# Papra_v0_20.net
KiCad netlist of a schematic drawn in EAGLE
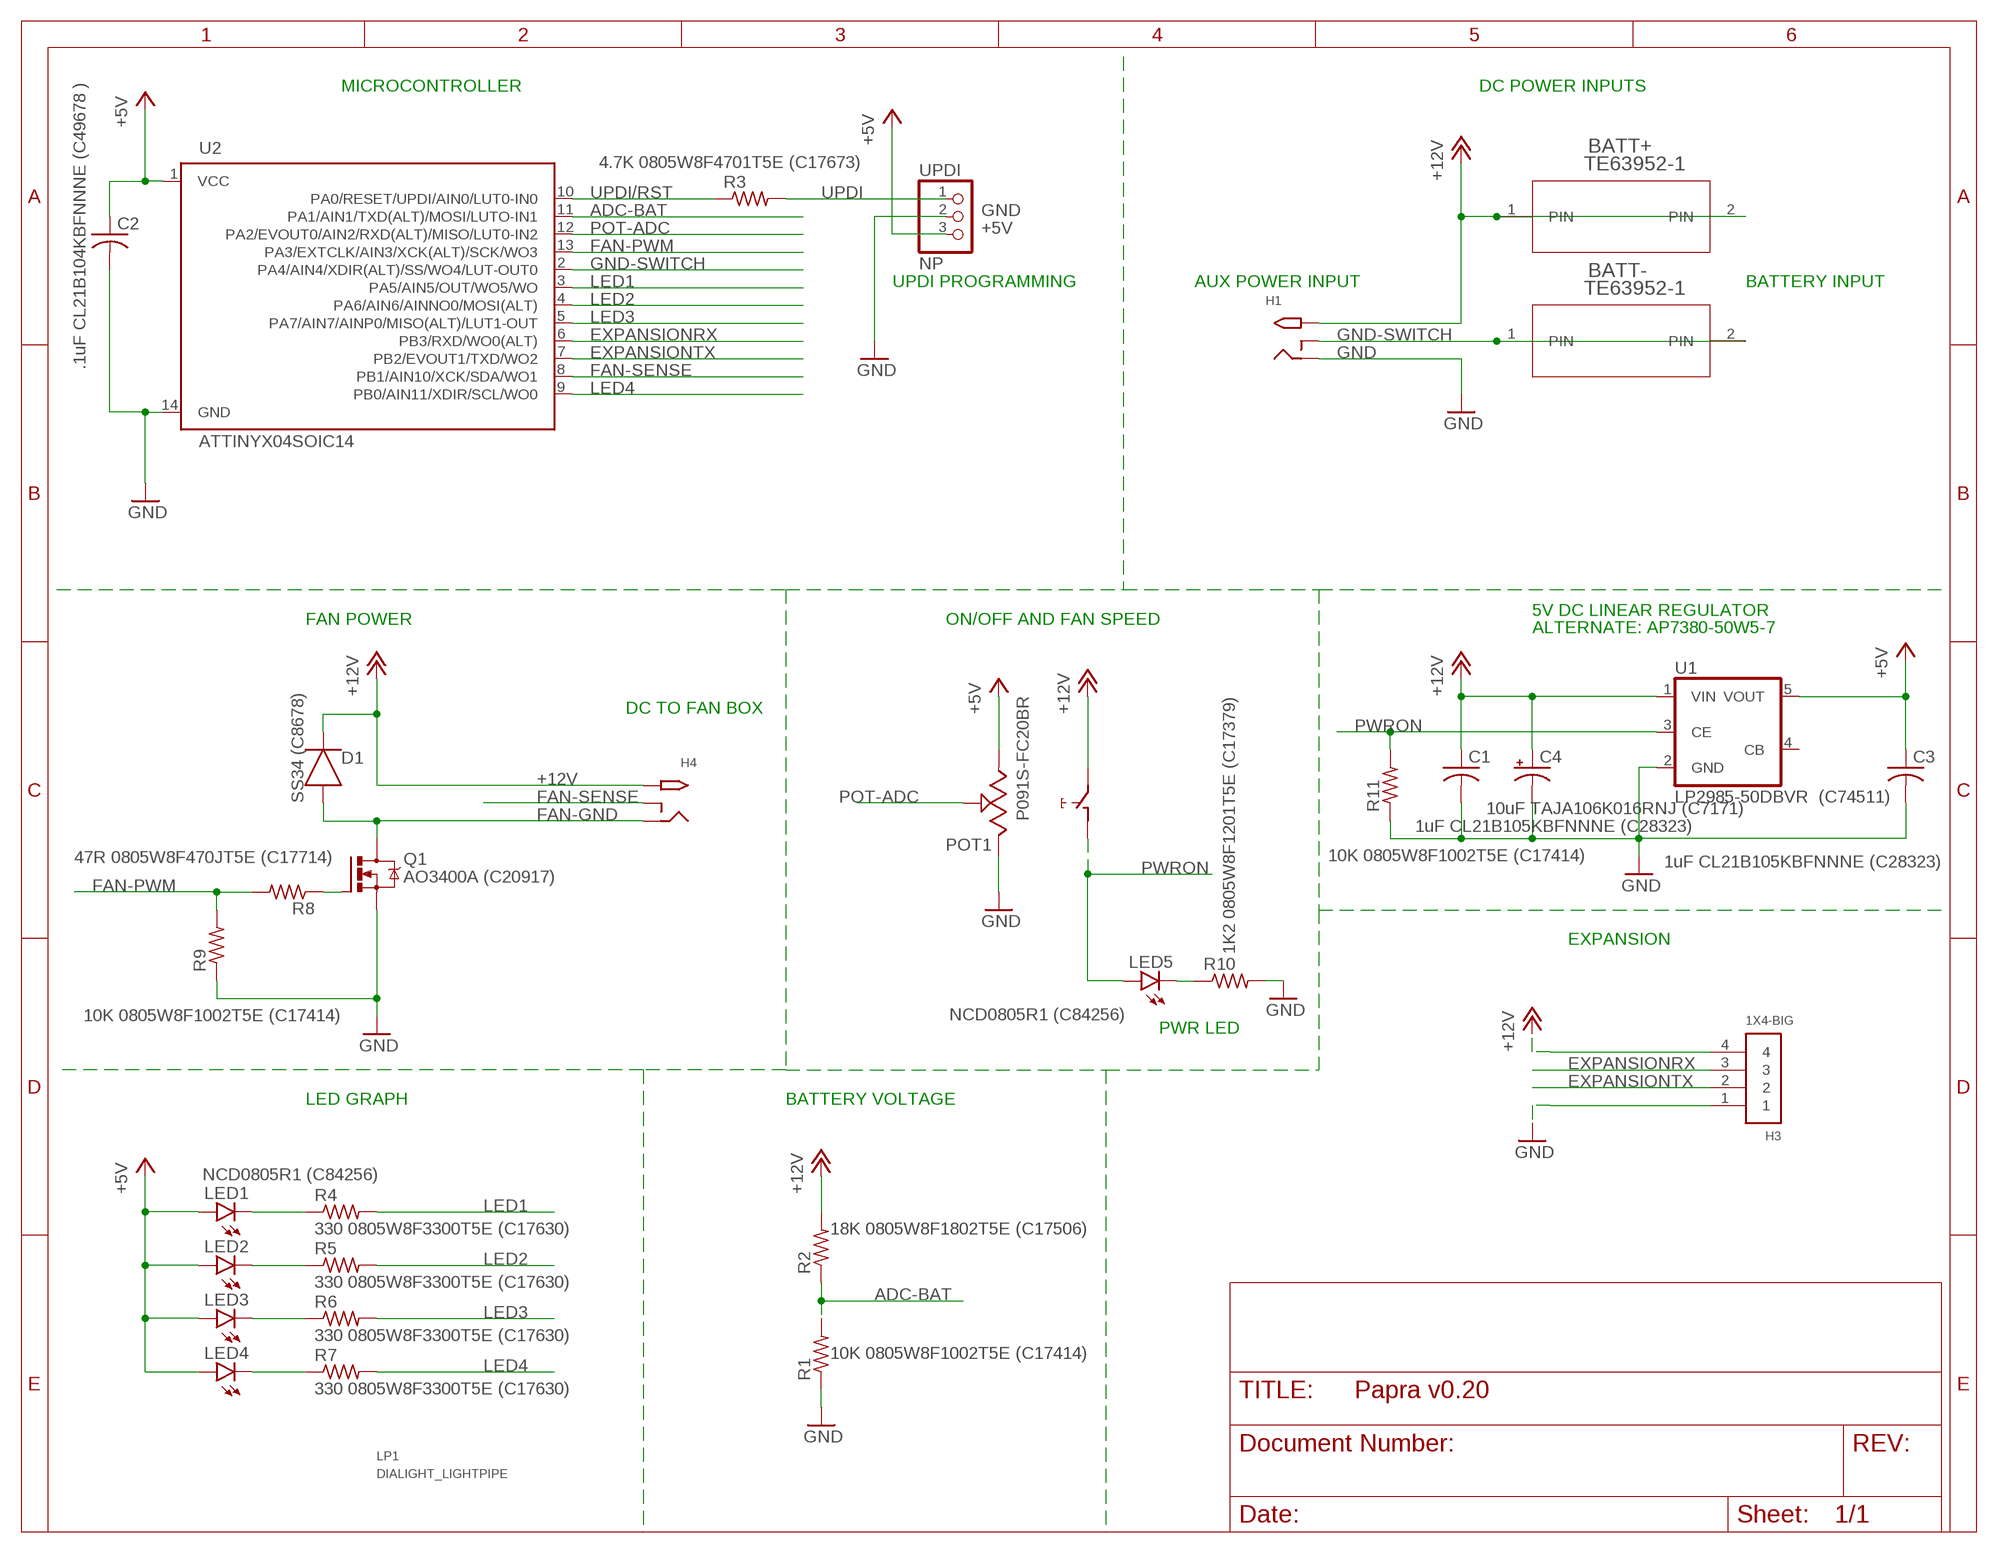
[diagram p0: schematic, sheet 1]

(export (version "E")
  (design (tool "Eeschema 10.0.6"))
  (components
    (comp (ref "BATT+")
      (value "TE63952-1")
      (footprint "eagle-import:TE63952-1")
      (libsource (lib "eagle-import") (part "TE63952-1"))
    )
    (comp (ref "BATT-")
      (value "TE63952-1")
      (footprint "eagle-import:TE63952-1")
      (libsource (lib "eagle-import") (part "TE63952-1"))
    )
    (comp (ref "C1")
      (value "1uF CL21B105KBFNNNE (C28323)")
      (footprint "eagle-import:C0805")
      (libsource (lib "eagle-import") (part "C-USC0805"))
    )
    (comp (ref "C2")
      (value ".1uF CL21B104KBFNNNE (C49678 )")
      (footprint "eagle-import:C0805")
      (libsource (lib "eagle-import") (part "C-USC0805"))
    )
    (comp (ref "C3")
      (value "1uF CL21B105KBFNNNE (C28323)")
      (footprint "eagle-import:C0805")
      (libsource (lib "eagle-import") (part "C-USC0805"))
    )
    (comp (ref "C4")
      (value "10uF TAJA106K016RNJ (C7171)")
      (footprint "eagle-import:A_3216-18R")
      (libsource (lib "eagle-import") (part "CPOL-USA/3216-18R"))
    )
    (comp (ref "D1")
      (value "SS34 (C8678)")
      (footprint "eagle-import:DIOM5226X290N")
      (libsource (lib "eagle-import") (part "DIODEDO-214AC(SMA)"))
    )
    (comp (ref "H1")
      (value "M-CUI-PJ-066A")
      (footprint "eagle-import:DCJACK-PJ-066A")
      (libsource (lib "eagle-import") (part "PJ-066A"))
    )
    (comp (ref "H3")
      (value "1X4-BIG")
      (footprint "eagle-import:1X04-BIG")
      (libsource (lib "eagle-import") (part "1X4-BIG"))
    )
    (comp (ref "H4")
      (value "M-CUI-PJ-066A")
      (footprint "eagle-import:DCJACK-PJ-066A")
      (libsource (lib "eagle-import") (part "PJ-066A"))
    )
    (comp (ref "LED1")
      (value "NCD0805R1 (C84256)")
      (footprint "eagle-import:CHIPLED_0805")
      (libsource (lib "eagle-import") (part "LEDCHIPLED_0805"))
    )
    (comp (ref "LED2")
      (value "NCD0805R1 (C84256)")
      (footprint "eagle-import:CHIPLED_0805")
      (libsource (lib "eagle-import") (part "LEDCHIPLED_0805"))
    )
    (comp (ref "LED3")
      (value "NCD0805R1 (C84256)")
      (footprint "eagle-import:CHIPLED_0805")
      (libsource (lib "eagle-import") (part "LEDCHIPLED_0805"))
    )
    (comp (ref "LED4")
      (value "NCD0805R1 (C84256)")
      (footprint "eagle-import:CHIPLED_0805")
      (libsource (lib "eagle-import") (part "LEDCHIPLED_0805"))
    )
    (comp (ref "LED5")
      (value "NCD0805R1 (C84256)")
      (footprint "eagle-import:CHIPLED_0805")
      (libsource (lib "eagle-import") (part "LEDCHIPLED_0805"))
    )
    (comp (ref "LP1")
      (value "DIALIGHT_LIGHTPIPE")
      (footprint "eagle-import:DIALIGHT_5151020F__LEDS")
      (libsource (lib "eagle-import") (part "DIALIGHT_LIGHTPIPE"))
    )
    (comp (ref "POT1")
      (value "P091S-FC20BR")
      (footprint "eagle-import:P091S-FC20BR")
      (libsource (lib "eagle-import") (part "P091S-FC20BR"))
    )
    (comp (ref "Q1")
      (value "AO3400A (C20917)")
      (footprint "eagle-import:SOT23")
      (fields (field (name "MANUFACTURER") "ON Semiconductor") (field (name "MPN") "BSS123L"))
      (libsource (lib "eagle-import") (part "NMOSFET_-SOT23BSS123"))
    )
    (comp (ref "R1")
      (value "10K 0805W8F1002T5E (C17414)")
      (footprint "eagle-import:R0805")
      (libsource (lib "eagle-import") (part "R-US_R0805"))
    )
    (comp (ref "R2")
      (value "18K 0805W8F1802T5E (C17506)")
      (footprint "eagle-import:R0805")
      (libsource (lib "eagle-import") (part "R-US_R0805"))
    )
    (comp (ref "R3")
      (value "4.7K 0805W8F4701T5E (C17673)")
      (footprint "eagle-import:R0805")
      (libsource (lib "eagle-import") (part "R-US_R0805"))
    )
    (comp (ref "R4")
      (value "330 0805W8F3300T5E (C17630)")
      (footprint "eagle-import:R0805")
      (libsource (lib "eagle-import") (part "R-US_R0805"))
    )
    (comp (ref "R5")
      (value "330 0805W8F3300T5E (C17630)")
      (footprint "eagle-import:R0805")
      (libsource (lib "eagle-import") (part "R-US_R0805"))
    )
    (comp (ref "R6")
      (value "330 0805W8F3300T5E (C17630)")
      (footprint "eagle-import:R0805")
      (libsource (lib "eagle-import") (part "R-US_R0805"))
    )
    (comp (ref "R7")
      (value "330 0805W8F3300T5E (C17630)")
      (footprint "eagle-import:R0805")
      (libsource (lib "eagle-import") (part "R-US_R0805"))
    )
    (comp (ref "R8")
      (value "47R 0805W8F470JT5E (C17714)")
      (footprint "eagle-import:R0805")
      (libsource (lib "eagle-import") (part "R-US_R0805"))
    )
    (comp (ref "R9")
      (value "10K 0805W8F1002T5E (C17414)")
      (footprint "eagle-import:R0805")
      (libsource (lib "eagle-import") (part "R-US_R0805"))
    )
    (comp (ref "R10")
      (value "1K2 0805W8F1201T5E (C17379)")
      (footprint "eagle-import:R0805")
      (libsource (lib "eagle-import") (part "R-US_R0805"))
    )
    (comp (ref "R11")
      (value "10K 0805W8F1002T5E (C17414)")
      (footprint "eagle-import:R0805")
      (libsource (lib "eagle-import") (part "R-US_R0805"))
    )
    (comp (ref "U1")
      (value "LP2985-50DBVR (C74511)")
      (footprint "eagle-import:SOT25")
      (libsource (lib "eagle-import") (part "TS520533"))
    )
    (comp (ref "U2")
      (value "ATTINYX04SOIC14")
      (footprint "eagle-import:SOIC127P600X144-14")
      (libsource (lib "eagle-import") (part "ATTINYX04SOIC14"))
    )
    (comp (ref "UPDI")
      (value "NP")
      (footprint "eagle-import:1X03")
      (libsource (lib "eagle-import") (part "PINHD-1X3"))
    )
  )
  (nets
    (net (code "1") (name "+5V") (class "Default")
      (node (ref "C2") (pin "1") (pinfunction "1_1") (pintype "passive"))
      (node (ref "C3") (pin "1") (pinfunction "1_1") (pintype "passive"))
      (node (ref "LED1") (pin "A") (pinfunction "A_A") (pintype "passive"))
      (node (ref "LED2") (pin "A") (pinfunction "A_A") (pintype "passive"))
      (node (ref "LED3") (pin "A") (pinfunction "A_A") (pintype "passive"))
      (node (ref "LED4") (pin "A") (pinfunction "A_A") (pintype "passive"))
      (node (ref "POT1") (pin "1") (pinfunction "1_1") (pintype "passive"))
      (node (ref "U1") (pin "5") (pinfunction "VOUT_5") (pintype "passive"))
      (node (ref "U2") (pin "1") (pinfunction "VCC_1") (pintype "power_in"))
      (node (ref "UPDI") (pin "3") (pinfunction "3_3") (pintype "passive"))
    )
    (net (code "2") (name "+12V") (class "Default")
      (node (ref "BATT+") (pin "1") (pinfunction "PIN_1") (pintype "passive"))
      (node (ref "BATT+") (pin "2") (pinfunction "PIN_2") (pintype "passive"))
      (node (ref "C1") (pin "1") (pinfunction "1_1") (pintype "passive"))
      (node (ref "C4") (pin "+") (pinfunction "+_+") (pintype "passive"))
      (node (ref "D1") (pin "1") (pinfunction "C_1") (pintype "passive"))
      (node (ref "H1") (pin "PWR") (pinfunction "TIP_PWR") (pintype "bidirectional"))
      (node (ref "H3") (pin "4") (pinfunction "4_4") (pintype "bidirectional"))
      (node (ref "H4") (pin "PWR") (pinfunction "TIP_PWR") (pintype "bidirectional"))
      (node (ref "POT1") (pin "NO") (pinfunction "5_NO") (pintype "passive"))
      (node (ref "R2") (pin "2") (pinfunction "2_2") (pintype "passive"))
      (node (ref "U1") (pin "1") (pinfunction "VIN_1") (pintype "input"))
    )
    (net (code "3") (name "/ADC-BAT") (class "Default")
      (node (ref "R1") (pin "2") (pinfunction "2_2") (pintype "passive"))
      (node (ref "R2") (pin "1") (pinfunction "1_1") (pintype "passive"))
      (node (ref "U2") (pin "11") (pinfunction "PA1/AIN1/TXD(ALT)/MOSI/LUTO-IN1_11") (pintype "bidirectional"))
    )
    (net (code "4") (name "/EXPANSIONRX") (class "Default")
      (node (ref "H3") (pin "3") (pinfunction "3_3") (pintype "bidirectional"))
      (node (ref "U2") (pin "6") (pinfunction "PB3/RXD/WO0(ALT)_6") (pintype "bidirectional"))
    )
    (net (code "5") (name "/EXPANSIONTX") (class "Default")
      (node (ref "H3") (pin "2") (pinfunction "2_2") (pintype "bidirectional"))
      (node (ref "U2") (pin "7") (pinfunction "PB2/EVOUT1/TXD/WO2_7") (pintype "bidirectional"))
    )
    (net (code "6") (name "/FAN-GND") (class "Default")
      (node (ref "D1") (pin "2") (pinfunction "A_2") (pintype "passive"))
      (node (ref "H4") (pin "GND") (pinfunction "RING_GND") (pintype "bidirectional"))
      (node (ref "Q1") (pin "3") (pinfunction "D_3") (pintype "passive"))
    )
    (net (code "7") (name "/FAN-PWM") (class "Default")
      (node (ref "R8") (pin "2") (pinfunction "2_2") (pintype "passive"))
      (node (ref "R9") (pin "2") (pinfunction "2_2") (pintype "passive"))
      (node (ref "U2") (pin "13") (pinfunction "PA3/EXTCLK/AIN3/XCK(ALT)/SCK/WO3_13") (pintype "bidirectional"))
    )
    (net (code "8") (name "/FAN-SENSE") (class "Default")
      (node (ref "H4") (pin "GNDBREAK") (pinfunction "RING_SW_GNDBREAK") (pintype "bidirectional"))
      (node (ref "U2") (pin "8") (pinfunction "PB1/AIN10/XCK/SDA/WO1_8") (pintype "bidirectional"))
    )
    (net (code "9") (name "/GND-SWITCH") (class "Default")
      (node (ref "BATT-") (pin "1") (pinfunction "PIN_1") (pintype "passive"))
      (node (ref "BATT-") (pin "2") (pinfunction "PIN_2") (pintype "passive"))
      (node (ref "H1") (pin "GNDBREAK") (pinfunction "RING_SW_GNDBREAK") (pintype "bidirectional"))
      (node (ref "U2") (pin "2") (pinfunction "PA4/AIN4/XDIR(ALT)/SS/WO4/LUT-OUT0_2") (pintype "bidirectional"))
    )
    (net (code "10") (name "/LED1") (class "Default")
      (node (ref "R4") (pin "2") (pinfunction "2_2") (pintype "passive"))
      (node (ref "U2") (pin "3") (pinfunction "PA5/AIN5/OUT/WO5/WO_3") (pintype "bidirectional"))
    )
    (net (code "11") (name "/LED2") (class "Default")
      (node (ref "R5") (pin "2") (pinfunction "2_2") (pintype "passive"))
      (node (ref "U2") (pin "4") (pinfunction "PA6/AIN6/AINNO0/MOSI(ALT)_4") (pintype "bidirectional"))
    )
    (net (code "12") (name "/LED3") (class "Default")
      (node (ref "R6") (pin "2") (pinfunction "2_2") (pintype "passive"))
      (node (ref "U2") (pin "5") (pinfunction "PA7/AIN7/AINP0/MISO(ALT)/LUT1-OUT_5") (pintype "bidirectional"))
    )
    (net (code "13") (name "/LED4") (class "Default")
      (node (ref "R7") (pin "2") (pinfunction "2_2") (pintype "passive"))
      (node (ref "U2") (pin "9") (pinfunction "PB0/AIN11/XDIR/SCL/WO0_9") (pintype "bidirectional"))
    )
    (net (code "14") (name "/POT-ADC") (class "Default")
      (node (ref "POT1") (pin "2") (pinfunction "2_2") (pintype "passive"))
      (node (ref "U2") (pin "12") (pinfunction "PA2/EVOUT0/AIN2/RXD(ALT)/MISO/LUT0-IN2_12") (pintype "bidirectional"))
    )
    (net (code "15") (name "/PWRON") (class "Default")
      (node (ref "LED5") (pin "A") (pinfunction "A_A") (pintype "passive"))
      (node (ref "POT1") (pin "COM") (pinfunction "4_COM") (pintype "passive"))
      (node (ref "R11") (pin "2") (pinfunction "2_2") (pintype "passive"))
      (node (ref "U1") (pin "3") (pinfunction "CE_3") (pintype "input"))
    )
    (net (code "16") (name "/UPDI") (class "Default")
      (node (ref "R3") (pin "2") (pinfunction "2_2") (pintype "passive"))
      (node (ref "UPDI") (pin "1") (pinfunction "1_1") (pintype "passive"))
    )
    (net (code "17") (name "/UPDI{slash}RST") (class "Default")
      (node (ref "R3") (pin "1") (pinfunction "1_1") (pintype "passive"))
      (node (ref "U2") (pin "10") (pinfunction "PA0/RESET/UPDI/AIN0/LUT0-IN0_10") (pintype "bidirectional"))
    )
    (net (code "18") (name "GND") (class "Default")
      (node (ref "C1") (pin "2") (pinfunction "2_2") (pintype "passive"))
      (node (ref "C2") (pin "2") (pinfunction "2_2") (pintype "passive"))
      (node (ref "C3") (pin "2") (pinfunction "2_2") (pintype "passive"))
      (node (ref "C4") (pin "-") (pinfunction "-_-") (pintype "passive"))
      (node (ref "H1") (pin "GND") (pinfunction "RING_GND") (pintype "bidirectional"))
      (node (ref "H3") (pin "1") (pinfunction "1_1") (pintype "bidirectional"))
      (node (ref "POT1") (pin "3") (pinfunction "3_3") (pintype "passive"))
      (node (ref "Q1") (pin "2") (pinfunction "S_2") (pintype "passive"))
      (node (ref "R1") (pin "1") (pinfunction "1_1") (pintype "passive"))
      (node (ref "R10") (pin "2") (pinfunction "2_2") (pintype "passive"))
      (node (ref "R11") (pin "1") (pinfunction "1_1") (pintype "passive"))
      (node (ref "R9") (pin "1") (pinfunction "1_1") (pintype "passive"))
      (node (ref "U1") (pin "2") (pinfunction "GND_2") (pintype "passive"))
      (node (ref "U2") (pin "14") (pinfunction "GND_14") (pintype "power_in"))
      (node (ref "UPDI") (pin "2") (pinfunction "2_2") (pintype "passive"))
    )
    (net (code "19") (name "Net-(LED1-PadC)") (class "Default")
      (node (ref "LED1") (pin "C") (pinfunction "C_C") (pintype "passive"))
      (node (ref "R4") (pin "1") (pinfunction "1_1") (pintype "passive"))
    )
    (net (code "20") (name "Net-(LED2-PadC)") (class "Default")
      (node (ref "LED2") (pin "C") (pinfunction "C_C") (pintype "passive"))
      (node (ref "R5") (pin "1") (pinfunction "1_1") (pintype "passive"))
    )
    (net (code "21") (name "Net-(LED3-PadC)") (class "Default")
      (node (ref "LED3") (pin "C") (pinfunction "C_C") (pintype "passive"))
      (node (ref "R6") (pin "1") (pinfunction "1_1") (pintype "passive"))
    )
    (net (code "22") (name "Net-(LED4-PadC)") (class "Default")
      (node (ref "LED4") (pin "C") (pinfunction "C_C") (pintype "passive"))
      (node (ref "R7") (pin "1") (pinfunction "1_1") (pintype "passive"))
    )
    (net (code "23") (name "Net-(LED5-PadC)") (class "Default")
      (node (ref "LED5") (pin "C") (pinfunction "C_C") (pintype "passive"))
      (node (ref "R10") (pin "1") (pinfunction "1_1") (pintype "passive"))
    )
    (net (code "24") (name "Net-(Q1-G)") (class "Default")
      (node (ref "Q1") (pin "1") (pinfunction "G_1") (pintype "passive"))
      (node (ref "R8") (pin "1") (pinfunction "1_1") (pintype "passive"))
    )
    (net (code "25") (name "unconnected-(U1-CB-Pad4)") (class "Default")
      (node (ref "U1") (pin "4") (pinfunction "CB_4") (pintype "input"))
    )
  )
)
